# Display-Board_Rack-PDU_2_0.net
KiCad netlist of a schematic drawn in EAGLE
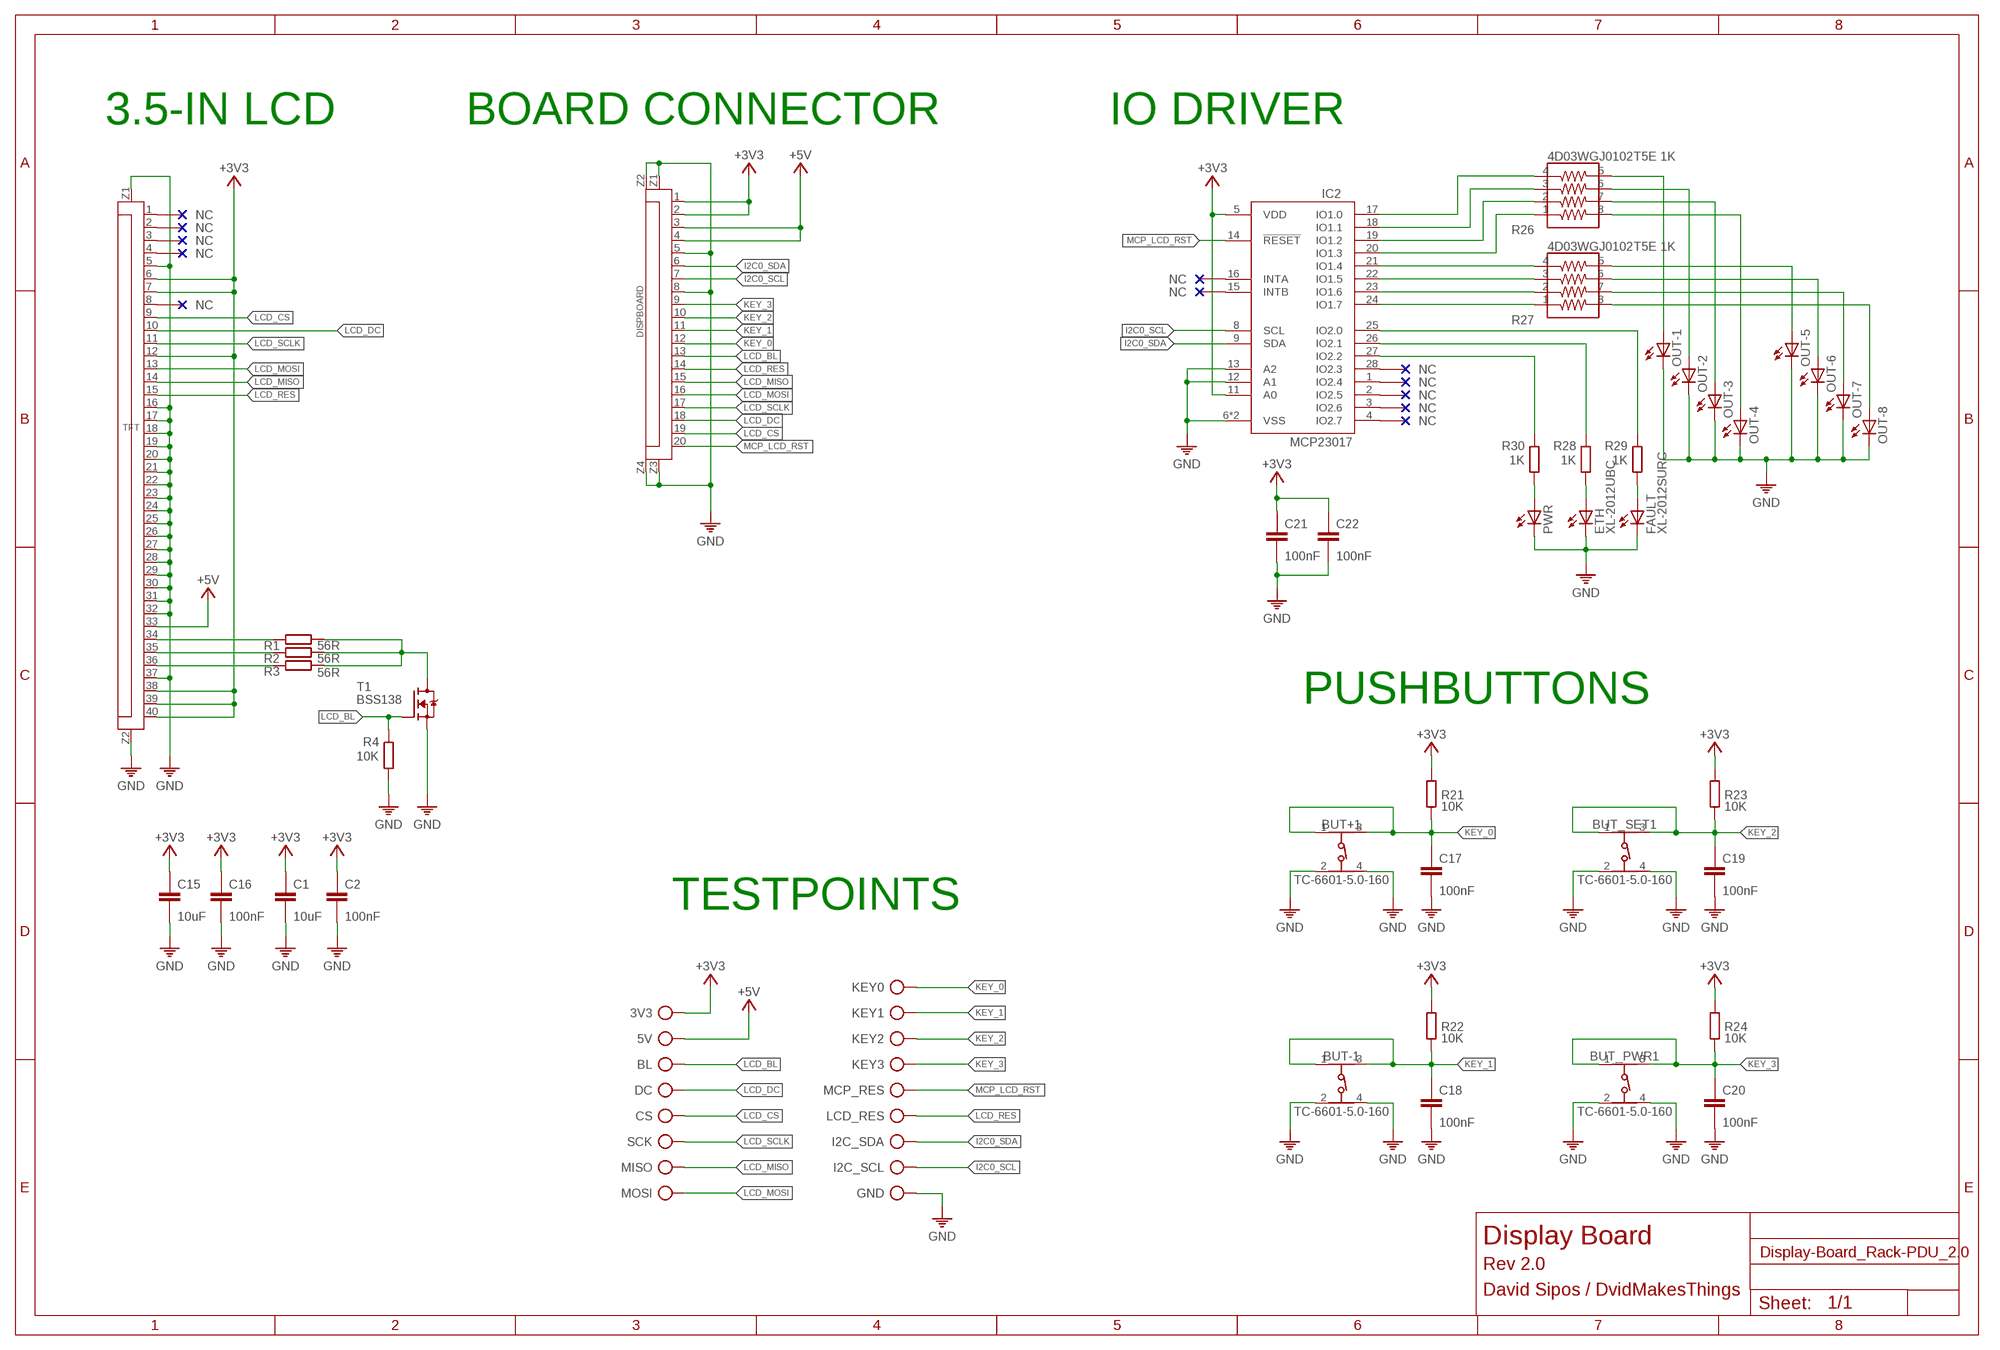
[diagram p0: schematic, sheet 1]

(export (version "E")
  (design (tool "Eeschema 10.0.6"))
  (components
    (comp (ref "3V3") (value "TP") (footprint "eagle-import:TP") (libsource (lib "eagle-import") (part "TP")))
    (comp (ref "5V") (value "TP") (footprint "eagle-import:TP") (libsource (lib "eagle-import") (part "TP")))
    (comp (ref "BL") (value "TP") (footprint "eagle-import:TP") (libsource (lib "eagle-import") (part "TP")))
    (comp (ref "BUT+1")
      (value "TC-6601-5.0-160")
      (footprint "eagle-import:430182043816")
      (libsource (lib "eagle-import") (part "430182043816"))
    )
    (comp (ref "BUT-1")
      (value "TC-6601-5.0-160")
      (footprint "eagle-import:430182043816")
      (libsource (lib "eagle-import") (part "430182043816"))
    )
    (comp (ref "BUT_PWR1")
      (value "TC-6601-5.0-160")
      (footprint "eagle-import:430182043816")
      (libsource (lib "eagle-import") (part "430182043816"))
    )
    (comp (ref "BUT_SET1")
      (value "TC-6601-5.0-160")
      (footprint "eagle-import:430182043816")
      (libsource (lib "eagle-import") (part "430182043816"))
    )
    (comp (ref "C1")
      (value "10uF")
      (footprint "eagle-import:C0402")
      (libsource (lib "eagle-import") (part "C-0402"))
    )
    (comp (ref "C2")
      (value "100nF")
      (footprint "eagle-import:C0402")
      (libsource (lib "eagle-import") (part "C-0402"))
    )
    (comp (ref "C15")
      (value "10uF")
      (footprint "eagle-import:C0402")
      (libsource (lib "eagle-import") (part "C-0402"))
    )
    (comp (ref "C16")
      (value "100nF")
      (footprint "eagle-import:C0402")
      (libsource (lib "eagle-import") (part "C-0402"))
    )
    (comp (ref "C17")
      (value "100nF")
      (footprint "eagle-import:C0402")
      (libsource (lib "eagle-import") (part "C-0402"))
    )
    (comp (ref "C18")
      (value "100nF")
      (footprint "eagle-import:C0402")
      (libsource (lib "eagle-import") (part "C-0402"))
    )
    (comp (ref "C19")
      (value "100nF")
      (footprint "eagle-import:C0402")
      (libsource (lib "eagle-import") (part "C-0402"))
    )
    (comp (ref "C20")
      (value "100nF")
      (footprint "eagle-import:C0402")
      (libsource (lib "eagle-import") (part "C-0402"))
    )
    (comp (ref "C21")
      (value "100nF")
      (footprint "eagle-import:C0402")
      (libsource (lib "eagle-import") (part "C-0402"))
    )
    (comp (ref "C22")
      (value "100nF")
      (footprint "eagle-import:C0402")
      (libsource (lib "eagle-import") (part "C-0402"))
    )
    (comp (ref "CS") (value "TP") (footprint "eagle-import:TP") (libsource (lib "eagle-import") (part "TP")))
    (comp (ref "DC") (value "TP") (footprint "eagle-import:TP") (libsource (lib "eagle-import") (part "TP")))
    (comp (ref "DISPBOARD")
      (value "FPC20-H")
      (footprint "eagle-import:FPC20")
      (libsource (lib "eagle-import") (part "FPC20-H"))
    )
    (comp (ref "ETH")
      (value "XL-2012UBC")
      (footprint "eagle-import:CHIP-LED0805")
      (libsource (lib "eagle-import") (part "LEDCHIP-LED0805"))
    )
    (comp (ref "FAULT")
      (value "XL-2012SURC")
      (footprint "eagle-import:CHIP-LED0805")
      (libsource (lib "eagle-import") (part "LEDCHIP-LED0805"))
    )
    (comp (ref "GND") (value "TP") (footprint "eagle-import:TP") (libsource (lib "eagle-import") (part "TP")))
    (comp (ref "I2C_SCL")
      (value "TP")
      (footprint "eagle-import:TP")
      (libsource (lib "eagle-import") (part "TP"))
    )
    (comp (ref "I2C_SDA")
      (value "TP")
      (footprint "eagle-import:TP")
      (libsource (lib "eagle-import") (part "TP"))
    )
    (comp (ref "IC2")
      (value "MCP23017-E/ML")
      (footprint "eagle-import:QFN28[6X6]ML")
      (libsource (lib "eagle-import") (part "MCP23017-E/ML"))
    )
    (comp (ref "KEY0")
      (value "TP")
      (footprint "eagle-import:TP")
      (libsource (lib "eagle-import") (part "TP"))
    )
    (comp (ref "KEY1")
      (value "TP")
      (footprint "eagle-import:TP")
      (libsource (lib "eagle-import") (part "TP"))
    )
    (comp (ref "KEY2")
      (value "TP")
      (footprint "eagle-import:TP")
      (libsource (lib "eagle-import") (part "TP"))
    )
    (comp (ref "KEY3")
      (value "TP")
      (footprint "eagle-import:TP")
      (libsource (lib "eagle-import") (part "TP"))
    )
    (comp (ref "LCD_RES")
      (value "TP")
      (footprint "eagle-import:TP")
      (libsource (lib "eagle-import") (part "TP"))
    )
    (comp (ref "MCP_RES")
      (value "TP")
      (footprint "eagle-import:TP")
      (libsource (lib "eagle-import") (part "TP"))
    )
    (comp (ref "MISO")
      (value "TP")
      (footprint "eagle-import:TP")
      (libsource (lib "eagle-import") (part "TP"))
    )
    (comp (ref "MOSI")
      (value "TP")
      (footprint "eagle-import:TP")
      (libsource (lib "eagle-import") (part "TP"))
    )
    (comp (ref "OUT-1")
      (value "LEDCHIP-LED0805")
      (footprint "eagle-import:CHIP-LED0805")
      (libsource (lib "eagle-import") (part "LEDCHIP-LED0805"))
    )
    (comp (ref "OUT-2")
      (value "LEDCHIP-LED0805")
      (footprint "eagle-import:CHIP-LED0805")
      (libsource (lib "eagle-import") (part "LEDCHIP-LED0805"))
    )
    (comp (ref "OUT-3")
      (value "LEDCHIP-LED0805")
      (footprint "eagle-import:CHIP-LED0805")
      (libsource (lib "eagle-import") (part "LEDCHIP-LED0805"))
    )
    (comp (ref "OUT-4")
      (value "LEDCHIP-LED0805")
      (footprint "eagle-import:CHIP-LED0805")
      (libsource (lib "eagle-import") (part "LEDCHIP-LED0805"))
    )
    (comp (ref "OUT-5")
      (value "LEDCHIP-LED0805")
      (footprint "eagle-import:CHIP-LED0805")
      (libsource (lib "eagle-import") (part "LEDCHIP-LED0805"))
    )
    (comp (ref "OUT-6")
      (value "LEDCHIP-LED0805")
      (footprint "eagle-import:CHIP-LED0805")
      (libsource (lib "eagle-import") (part "LEDCHIP-LED0805"))
    )
    (comp (ref "OUT-7")
      (value "LEDCHIP-LED0805")
      (footprint "eagle-import:CHIP-LED0805")
      (libsource (lib "eagle-import") (part "LEDCHIP-LED0805"))
    )
    (comp (ref "OUT-8")
      (value "LEDCHIP-LED0805")
      (footprint "eagle-import:CHIP-LED0805")
      (libsource (lib "eagle-import") (part "LEDCHIP-LED0805"))
    )
    (comp (ref "PWR")
      (value "LEDCHIP-LED0805")
      (footprint "eagle-import:CHIP-LED0805")
      (libsource (lib "eagle-import") (part "LEDCHIP-LED0805"))
    )
    (comp (ref "R1")
      (value "56R")
      (footprint "eagle-import:0402")
      (libsource (lib "eagle-import") (part "R0402"))
    )
    (comp (ref "R2")
      (value "56R")
      (footprint "eagle-import:0402")
      (libsource (lib "eagle-import") (part "R0402"))
    )
    (comp (ref "R3")
      (value "56R")
      (footprint "eagle-import:0402")
      (libsource (lib "eagle-import") (part "R0402"))
    )
    (comp (ref "R4")
      (value "10K")
      (footprint "eagle-import:0402")
      (libsource (lib "eagle-import") (part "R0402"))
    )
    (comp (ref "R21")
      (value "10K")
      (footprint "eagle-import:0402")
      (libsource (lib "eagle-import") (part "R0402"))
    )
    (comp (ref "R22")
      (value "10K")
      (footprint "eagle-import:0402")
      (libsource (lib "eagle-import") (part "R0402"))
    )
    (comp (ref "R23")
      (value "10K")
      (footprint "eagle-import:0402")
      (libsource (lib "eagle-import") (part "R0402"))
    )
    (comp (ref "R24")
      (value "10K")
      (footprint "eagle-import:0402")
      (libsource (lib "eagle-import") (part "R0402"))
    )
    (comp (ref "R26")
      (value "4D03WGJ0102T5E 1K")
      (footprint "eagle-import:742C083103JP")
      (fields
        (field (name "MANUFACTURER") "CTS Resistor Products")
        (field (name "MPN") "742C083103JP")
        (field (name "CREATED_BY") "PCBLayout.com")
      )
      (libsource (lib "eagle-import") (part "742C083103JP"))
    )
    (comp (ref "R27")
      (value "4D03WGJ0102T5E 1K")
      (footprint "eagle-import:742C083103JP")
      (fields
        (field (name "MANUFACTURER") "CTS Resistor Products")
        (field (name "MPN") "742C083103JP")
        (field (name "CREATED_BY") "PCBLayout.com")
      )
      (libsource (lib "eagle-import") (part "742C083103JP"))
    )
    (comp (ref "R28")
      (value "1K")
      (footprint "eagle-import:0402")
      (libsource (lib "eagle-import") (part "R0402"))
    )
    (comp (ref "R29")
      (value "1K")
      (footprint "eagle-import:0402")
      (libsource (lib "eagle-import") (part "R0402"))
    )
    (comp (ref "R30")
      (value "1K")
      (footprint "eagle-import:0402")
      (libsource (lib "eagle-import") (part "R0402"))
    )
    (comp (ref "SCK") (value "TP") (footprint "eagle-import:TP") (libsource (lib "eagle-import") (part "TP")))
    (comp (ref "T1")
      (value "BSS138")
      (footprint "eagle-import:SOT23")
      (libsource (lib "eagle-import") (part "BSS138"))
    )
    (comp (ref "TFT")
      (value "FPC40-HD")
      (footprint "eagle-import:FPC40_3.5TFT")
      (libsource (lib "eagle-import") (part "FPC40-HD"))
    )
  )
  (nets
    (net (code "1") (name "+3V3") (class "Default")
      (node (ref "3V3") (pin "TP") (pinfunction "P$1_TP") (pintype "bidirectional"))
      (node (ref "C1") (pin "1") (pinfunction "1_1") (pintype "passive"))
      (node (ref "C15") (pin "1") (pinfunction "1_1") (pintype "passive"))
      (node (ref "C16") (pin "1") (pinfunction "1_1") (pintype "passive"))
      (node (ref "C2") (pin "1") (pinfunction "1_1") (pintype "passive"))
      (node (ref "C21") (pin "1") (pinfunction "1_1") (pintype "passive"))
      (node (ref "C22") (pin "1") (pinfunction "1_1") (pintype "passive"))
      (node (ref "DISPBOARD") (pin "1") (pinfunction "1_1") (pintype "bidirectional"))
      (node (ref "DISPBOARD") (pin "2") (pinfunction "2_2") (pintype "bidirectional"))
      (node (ref "IC2") (pin "11") (pinfunction "A0_11") (pintype "bidirectional"))
      (node (ref "IC2") (pin "5") (pinfunction "VDD_5") (pintype "bidirectional"))
      (node (ref "R21") (pin "1") (pinfunction "1_1") (pintype "passive"))
      (node (ref "R22") (pin "1") (pinfunction "1_1") (pintype "passive"))
      (node (ref "R23") (pin "1") (pinfunction "1_1") (pintype "passive"))
      (node (ref "R24") (pin "1") (pinfunction "1_1") (pintype "passive"))
      (node (ref "TFT") (pin "12") (pinfunction "12_12") (pintype "bidirectional"))
      (node (ref "TFT") (pin "38") (pinfunction "38_38") (pintype "bidirectional"))
      (node (ref "TFT") (pin "39") (pinfunction "39_39") (pintype "bidirectional"))
      (node (ref "TFT") (pin "40") (pinfunction "40_40") (pintype "bidirectional"))
      (node (ref "TFT") (pin "6") (pinfunction "6_6") (pintype "bidirectional"))
      (node (ref "TFT") (pin "7") (pinfunction "7_7") (pintype "bidirectional"))
    )
    (net (code "2") (name "+5V") (class "Default")
      (node (ref "5V") (pin "TP") (pinfunction "P$1_TP") (pintype "bidirectional"))
      (node (ref "DISPBOARD") (pin "3") (pinfunction "3_3") (pintype "bidirectional"))
      (node (ref "DISPBOARD") (pin "4") (pinfunction "4_4") (pintype "bidirectional"))
      (node (ref "TFT") (pin "33") (pinfunction "33_33") (pintype "bidirectional"))
    )
    (net (code "3") (name "GND") (class "Default")
      (node (ref "BUT+1") (pin "2") (pinfunction "2_2") (pintype "passive"))
      (node (ref "BUT+1") (pin "4") (pinfunction "4_4") (pintype "passive"))
      (node (ref "BUT-1") (pin "2") (pinfunction "2_2") (pintype "passive"))
      (node (ref "BUT-1") (pin "4") (pinfunction "4_4") (pintype "passive"))
      (node (ref "BUT_PWR1") (pin "2") (pinfunction "2_2") (pintype "passive"))
      (node (ref "BUT_PWR1") (pin "4") (pinfunction "4_4") (pintype "passive"))
      (node (ref "BUT_SET1") (pin "2") (pinfunction "2_2") (pintype "passive"))
      (node (ref "BUT_SET1") (pin "4") (pinfunction "4_4") (pintype "passive"))
      (node (ref "C1") (pin "2") (pinfunction "2_2") (pintype "passive"))
      (node (ref "C15") (pin "2") (pinfunction "2_2") (pintype "passive"))
      (node (ref "C16") (pin "2") (pinfunction "2_2") (pintype "passive"))
      (node (ref "C17") (pin "2") (pinfunction "2_2") (pintype "passive"))
      (node (ref "C18") (pin "2") (pinfunction "2_2") (pintype "passive"))
      (node (ref "C19") (pin "2") (pinfunction "2_2") (pintype "passive"))
      (node (ref "C2") (pin "2") (pinfunction "2_2") (pintype "passive"))
      (node (ref "C20") (pin "2") (pinfunction "2_2") (pintype "passive"))
      (node (ref "C21") (pin "2") (pinfunction "2_2") (pintype "passive"))
      (node (ref "C22") (pin "2") (pinfunction "2_2") (pintype "passive"))
      (node (ref "DISPBOARD") (pin "5") (pinfunction "5_5") (pintype "bidirectional"))
      (node (ref "DISPBOARD") (pin "8") (pinfunction "8_8") (pintype "bidirectional"))
      (node (ref "DISPBOARD") (pin "Z1") (pinfunction "Z1_Z1") (pintype "bidirectional"))
      (node (ref "DISPBOARD") (pin "Z2") (pinfunction "Z2_Z2") (pintype "bidirectional"))
      (node (ref "DISPBOARD") (pin "Z3") (pinfunction "Z3_Z3") (pintype "bidirectional"))
      (node (ref "DISPBOARD") (pin "Z4") (pinfunction "Z4_Z4") (pintype "bidirectional"))
      (node (ref "ETH") (pin "C") (pinfunction "C_C") (pintype "passive"))
      (node (ref "FAULT") (pin "C") (pinfunction "C_C") (pintype "passive"))
      (node (ref "GND") (pin "TP") (pinfunction "P$1_TP") (pintype "bidirectional"))
      (node (ref "IC2") (pin "12") (pinfunction "A1_12") (pintype "bidirectional"))
      (node (ref "IC2") (pin "13") (pinfunction "A2_13") (pintype "bidirectional"))
      (node (ref "IC2") (pin "6") (pinfunction "VSS_6") (pintype "bidirectional"))
      (node (ref "IC2") (pin "PAD") (pinfunction "VSS_PAD") (pintype "bidirectional"))
      (node (ref "OUT-1") (pin "C") (pinfunction "C_C") (pintype "passive"))
      (node (ref "OUT-2") (pin "C") (pinfunction "C_C") (pintype "passive"))
      (node (ref "OUT-3") (pin "C") (pinfunction "C_C") (pintype "passive"))
      (node (ref "OUT-4") (pin "C") (pinfunction "C_C") (pintype "passive"))
      (node (ref "OUT-5") (pin "C") (pinfunction "C_C") (pintype "passive"))
      (node (ref "OUT-6") (pin "C") (pinfunction "C_C") (pintype "passive"))
      (node (ref "OUT-7") (pin "C") (pinfunction "C_C") (pintype "passive"))
      (node (ref "OUT-8") (pin "C") (pinfunction "C_C") (pintype "passive"))
      (node (ref "PWR") (pin "C") (pinfunction "C_C") (pintype "passive"))
      (node (ref "R4") (pin "2") (pinfunction "2_2") (pintype "passive"))
      (node (ref "T1") (pin "2") (pinfunction "S_2") (pintype "passive"))
      (node (ref "TFT") (pin "16") (pinfunction "16_16") (pintype "bidirectional"))
      (node (ref "TFT") (pin "17") (pinfunction "17_17") (pintype "bidirectional"))
      (node (ref "TFT") (pin "18") (pinfunction "18_18") (pintype "bidirectional"))
      (node (ref "TFT") (pin "19") (pinfunction "19_19") (pintype "bidirectional"))
      (node (ref "TFT") (pin "20") (pinfunction "20_20") (pintype "bidirectional"))
      (node (ref "TFT") (pin "21") (pinfunction "21_21") (pintype "bidirectional"))
      (node (ref "TFT") (pin "22") (pinfunction "22_22") (pintype "bidirectional"))
      (node (ref "TFT") (pin "23") (pinfunction "23_23") (pintype "bidirectional"))
      (node (ref "TFT") (pin "24") (pinfunction "24_24") (pintype "bidirectional"))
      (node (ref "TFT") (pin "25") (pinfunction "25_25") (pintype "bidirectional"))
      (node (ref "TFT") (pin "26") (pinfunction "26_26") (pintype "bidirectional"))
      (node (ref "TFT") (pin "27") (pinfunction "27_27") (pintype "bidirectional"))
      (node (ref "TFT") (pin "28") (pinfunction "28_28") (pintype "bidirectional"))
      (node (ref "TFT") (pin "29") (pinfunction "29_29") (pintype "bidirectional"))
      (node (ref "TFT") (pin "30") (pinfunction "30_30") (pintype "bidirectional"))
      (node (ref "TFT") (pin "31") (pinfunction "31_31") (pintype "bidirectional"))
      (node (ref "TFT") (pin "32") (pinfunction "32_32") (pintype "bidirectional"))
      (node (ref "TFT") (pin "37") (pinfunction "37_37") (pintype "bidirectional"))
      (node (ref "TFT") (pin "5") (pinfunction "5_5") (pintype "bidirectional"))
      (node (ref "TFT") (pin "Z1") (pinfunction "Z1_Z1") (pintype "bidirectional"))
      (node (ref "TFT") (pin "Z2") (pinfunction "Z2_Z2") (pintype "bidirectional"))
    )
    (net (code "4") (name "I2C0_SCL") (class "Default")
      (node (ref "DISPBOARD") (pin "7") (pinfunction "7_7") (pintype "bidirectional"))
      (node (ref "I2C_SCL") (pin "TP") (pinfunction "P$1_TP") (pintype "bidirectional"))
      (node (ref "IC2") (pin "8") (pinfunction "SCL_8") (pintype "bidirectional"))
    )
    (net (code "5") (name "I2C0_SDA") (class "Default")
      (node (ref "DISPBOARD") (pin "6") (pinfunction "6_6") (pintype "bidirectional"))
      (node (ref "I2C_SDA") (pin "TP") (pinfunction "P$1_TP") (pintype "bidirectional"))
      (node (ref "IC2") (pin "9") (pinfunction "SDA_9") (pintype "bidirectional"))
    )
    (net (code "6") (name "KEY_0") (class "Default")
      (node (ref "BUT+1") (pin "1") (pinfunction "1_1") (pintype "passive"))
      (node (ref "BUT+1") (pin "3") (pinfunction "3_3") (pintype "passive"))
      (node (ref "C17") (pin "1") (pinfunction "1_1") (pintype "passive"))
      (node (ref "DISPBOARD") (pin "12") (pinfunction "12_12") (pintype "bidirectional"))
      (node (ref "KEY0") (pin "TP") (pinfunction "P$1_TP") (pintype "bidirectional"))
      (node (ref "R21") (pin "2") (pinfunction "2_2") (pintype "passive"))
    )
    (net (code "7") (name "KEY_1") (class "Default")
      (node (ref "BUT-1") (pin "1") (pinfunction "1_1") (pintype "passive"))
      (node (ref "BUT-1") (pin "3") (pinfunction "3_3") (pintype "passive"))
      (node (ref "C18") (pin "1") (pinfunction "1_1") (pintype "passive"))
      (node (ref "DISPBOARD") (pin "11") (pinfunction "11_11") (pintype "bidirectional"))
      (node (ref "KEY1") (pin "TP") (pinfunction "P$1_TP") (pintype "bidirectional"))
      (node (ref "R22") (pin "2") (pinfunction "2_2") (pintype "passive"))
    )
    (net (code "8") (name "KEY_2") (class "Default")
      (node (ref "BUT_SET1") (pin "1") (pinfunction "1_1") (pintype "passive"))
      (node (ref "BUT_SET1") (pin "3") (pinfunction "3_3") (pintype "passive"))
      (node (ref "C19") (pin "1") (pinfunction "1_1") (pintype "passive"))
      (node (ref "DISPBOARD") (pin "10") (pinfunction "10_10") (pintype "bidirectional"))
      (node (ref "KEY2") (pin "TP") (pinfunction "P$1_TP") (pintype "bidirectional"))
      (node (ref "R23") (pin "2") (pinfunction "2_2") (pintype "passive"))
    )
    (net (code "9") (name "KEY_3") (class "Default")
      (node (ref "BUT_PWR1") (pin "1") (pinfunction "1_1") (pintype "passive"))
      (node (ref "BUT_PWR1") (pin "3") (pinfunction "3_3") (pintype "passive"))
      (node (ref "C20") (pin "1") (pinfunction "1_1") (pintype "passive"))
      (node (ref "DISPBOARD") (pin "9") (pinfunction "9_9") (pintype "bidirectional"))
      (node (ref "KEY3") (pin "TP") (pinfunction "P$1_TP") (pintype "bidirectional"))
      (node (ref "R24") (pin "2") (pinfunction "2_2") (pintype "passive"))
    )
    (net (code "10") (name "LCD_BL") (class "Default")
      (node (ref "BL") (pin "TP") (pinfunction "P$1_TP") (pintype "bidirectional"))
      (node (ref "DISPBOARD") (pin "13") (pinfunction "13_13") (pintype "bidirectional"))
      (node (ref "R4") (pin "1") (pinfunction "1_1") (pintype "passive"))
      (node (ref "T1") (pin "1") (pinfunction "G_1") (pintype "passive"))
    )
    (net (code "11") (name "LCD_CS") (class "Default")
      (node (ref "CS") (pin "TP") (pinfunction "P$1_TP") (pintype "bidirectional"))
      (node (ref "DISPBOARD") (pin "19") (pinfunction "19_19") (pintype "bidirectional"))
      (node (ref "TFT") (pin "9") (pinfunction "9_9") (pintype "bidirectional"))
    )
    (net (code "12") (name "LCD_DC") (class "Default")
      (node (ref "DC") (pin "TP") (pinfunction "P$1_TP") (pintype "bidirectional"))
      (node (ref "DISPBOARD") (pin "18") (pinfunction "18_18") (pintype "bidirectional"))
      (node (ref "TFT") (pin "10") (pinfunction "10_10") (pintype "bidirectional"))
    )
    (net (code "13") (name "LCD_MISO") (class "Default")
      (node (ref "DISPBOARD") (pin "15") (pinfunction "15_15") (pintype "bidirectional"))
      (node (ref "MISO") (pin "TP") (pinfunction "P$1_TP") (pintype "bidirectional"))
      (node (ref "TFT") (pin "14") (pinfunction "14_14") (pintype "bidirectional"))
    )
    (net (code "14") (name "LCD_MOSI") (class "Default")
      (node (ref "DISPBOARD") (pin "16") (pinfunction "16_16") (pintype "bidirectional"))
      (node (ref "MOSI") (pin "TP") (pinfunction "P$1_TP") (pintype "bidirectional"))
      (node (ref "TFT") (pin "13") (pinfunction "13_13") (pintype "bidirectional"))
    )
    (net (code "15") (name "LCD_RES") (class "Default")
      (node (ref "DISPBOARD") (pin "14") (pinfunction "14_14") (pintype "bidirectional"))
      (node (ref "LCD_RES") (pin "TP") (pinfunction "P$1_TP") (pintype "bidirectional"))
      (node (ref "TFT") (pin "15") (pinfunction "15_15") (pintype "bidirectional"))
    )
    (net (code "16") (name "LCD_SCLK") (class "Default")
      (node (ref "DISPBOARD") (pin "17") (pinfunction "17_17") (pintype "bidirectional"))
      (node (ref "SCK") (pin "TP") (pinfunction "P$1_TP") (pintype "bidirectional"))
      (node (ref "TFT") (pin "11") (pinfunction "11_11") (pintype "bidirectional"))
    )
    (net (code "17") (name "MCP_LCD_RST") (class "Default")
      (node (ref "DISPBOARD") (pin "20") (pinfunction "20_20") (pintype "bidirectional"))
      (node (ref "IC2") (pin "14") (pinfunction "~{RESET}_14") (pintype "bidirectional"))
      (node (ref "MCP_RES") (pin "TP") (pinfunction "P$1_TP") (pintype "bidirectional"))
    )
    (net (code "18") (name "Net-(ETH-PadA)") (class "Default")
      (node (ref "ETH") (pin "A") (pinfunction "A_A") (pintype "passive"))
      (node (ref "R28") (pin "2") (pinfunction "2_2") (pintype "passive"))
    )
    (net (code "19") (name "Net-(FAULT-PadA)") (class "Default")
      (node (ref "FAULT") (pin "A") (pinfunction "A_A") (pintype "passive"))
      (node (ref "R29") (pin "2") (pinfunction "2_2") (pintype "passive"))
    )
    (net (code "20") (name "Net-(IC2-IO1.0)") (class "Default")
      (node (ref "IC2") (pin "17") (pinfunction "IO1.0_17") (pintype "bidirectional"))
      (node (ref "R26") (pin "4") (pinfunction "4_4") (pintype "passive"))
    )
    (net (code "21") (name "Net-(IC2-IO1.1)") (class "Default")
      (node (ref "IC2") (pin "18") (pinfunction "IO1.1_18") (pintype "bidirectional"))
      (node (ref "R26") (pin "3") (pinfunction "3_3") (pintype "passive"))
    )
    (net (code "22") (name "Net-(IC2-IO1.2)") (class "Default")
      (node (ref "IC2") (pin "19") (pinfunction "IO1.2_19") (pintype "bidirectional"))
      (node (ref "R26") (pin "2") (pinfunction "2_2") (pintype "passive"))
    )
    (net (code "23") (name "Net-(IC2-IO1.3)") (class "Default")
      (node (ref "IC2") (pin "20") (pinfunction "IO1.3_20") (pintype "bidirectional"))
      (node (ref "R26") (pin "1") (pinfunction "1_1") (pintype "passive"))
    )
    (net (code "24") (name "Net-(IC2-IO1.4)") (class "Default")
      (node (ref "IC2") (pin "21") (pinfunction "IO1.4_21") (pintype "bidirectional"))
      (node (ref "R27") (pin "4") (pinfunction "4_4") (pintype "passive"))
    )
    (net (code "25") (name "Net-(IC2-IO1.5)") (class "Default")
      (node (ref "IC2") (pin "22") (pinfunction "IO1.5_22") (pintype "bidirectional"))
      (node (ref "R27") (pin "3") (pinfunction "3_3") (pintype "passive"))
    )
    (net (code "26") (name "Net-(IC2-IO1.6)") (class "Default")
      (node (ref "IC2") (pin "23") (pinfunction "IO1.6_23") (pintype "bidirectional"))
      (node (ref "R27") (pin "2") (pinfunction "2_2") (pintype "passive"))
    )
    (net (code "27") (name "Net-(IC2-IO1.7)") (class "Default")
      (node (ref "IC2") (pin "24") (pinfunction "IO1.7_24") (pintype "bidirectional"))
      (node (ref "R27") (pin "1") (pinfunction "1_1") (pintype "passive"))
    )
    (net (code "28") (name "Net-(IC2-IO2.0)") (class "Default")
      (node (ref "IC2") (pin "25") (pinfunction "IO2.0_25") (pintype "bidirectional"))
      (node (ref "R29") (pin "1") (pinfunction "1_1") (pintype "passive"))
    )
    (net (code "29") (name "Net-(IC2-IO2.1)") (class "Default")
      (node (ref "IC2") (pin "26") (pinfunction "IO2.1_26") (pintype "bidirectional"))
      (node (ref "R28") (pin "1") (pinfunction "1_1") (pintype "passive"))
    )
    (net (code "30") (name "Net-(IC2-IO2.2)") (class "Default")
      (node (ref "IC2") (pin "27") (pinfunction "IO2.2_27") (pintype "bidirectional"))
      (node (ref "R30") (pin "1") (pinfunction "1_1") (pintype "passive"))
    )
    (net (code "31") (name "Net-(OUT-1-PadA)") (class "Default")
      (node (ref "OUT-1") (pin "A") (pinfunction "A_A") (pintype "passive"))
      (node (ref "R26") (pin "5") (pinfunction "5_5") (pintype "passive"))
    )
    (net (code "32") (name "Net-(OUT-2-PadA)") (class "Default")
      (node (ref "OUT-2") (pin "A") (pinfunction "A_A") (pintype "passive"))
      (node (ref "R26") (pin "6") (pinfunction "6_6") (pintype "passive"))
    )
    (net (code "33") (name "Net-(OUT-3-PadA)") (class "Default")
      (node (ref "OUT-3") (pin "A") (pinfunction "A_A") (pintype "passive"))
      (node (ref "R26") (pin "7") (pinfunction "7_7") (pintype "passive"))
    )
    (net (code "34") (name "Net-(OUT-4-PadA)") (class "Default")
      (node (ref "OUT-4") (pin "A") (pinfunction "A_A") (pintype "passive"))
      (node (ref "R26") (pin "8") (pinfunction "8_8") (pintype "passive"))
    )
    (net (code "35") (name "Net-(OUT-5-PadA)") (class "Default")
      (node (ref "OUT-5") (pin "A") (pinfunction "A_A") (pintype "passive"))
      (node (ref "R27") (pin "5") (pinfunction "5_5") (pintype "passive"))
    )
    (net (code "36") (name "Net-(OUT-6-PadA)") (class "Default")
      (node (ref "OUT-6") (pin "A") (pinfunction "A_A") (pintype "passive"))
      (node (ref "R27") (pin "6") (pinfunction "6_6") (pintype "passive"))
    )
    (net (code "37") (name "Net-(OUT-7-PadA)") (class "Default")
      (node (ref "OUT-7") (pin "A") (pinfunction "A_A") (pintype "passive"))
      (node (ref "R27") (pin "7") (pinfunction "7_7") (pintype "passive"))
    )
    (net (code "38") (name "Net-(OUT-8-PadA)") (class "Default")
      (node (ref "OUT-8") (pin "A") (pinfunction "A_A") (pintype "passive"))
      (node (ref "R27") (pin "8") (pinfunction "8_8") (pintype "passive"))
    )
    (net (code "39") (name "Net-(PWR-PadA)") (class "Default")
      (node (ref "PWR") (pin "A") (pinfunction "A_A") (pintype "passive"))
      (node (ref "R30") (pin "2") (pinfunction "2_2") (pintype "passive"))
    )
    (net (code "40") (name "Net-(R1-Pad2)") (class "Default")
      (node (ref "R1") (pin "2") (pinfunction "2_2") (pintype "passive"))
      (node (ref "TFT") (pin "34") (pinfunction "34_34") (pintype "bidirectional"))
    )
    (net (code "41") (name "Net-(R2-Pad2)") (class "Default")
      (node (ref "R2") (pin "2") (pinfunction "2_2") (pintype "passive"))
      (node (ref "TFT") (pin "35") (pinfunction "35_35") (pintype "bidirectional"))
    )
    (net (code "42") (name "Net-(R3-Pad2)") (class "Default")
      (node (ref "R3") (pin "2") (pinfunction "2_2") (pintype "passive"))
      (node (ref "TFT") (pin "36") (pinfunction "36_36") (pintype "bidirectional"))
    )
    (net (code "43") (name "Net-(T1-D)") (class "Default")
      (node (ref "R1") (pin "1") (pinfunction "1_1") (pintype "passive"))
      (node (ref "R2") (pin "1") (pinfunction "1_1") (pintype "passive"))
      (node (ref "R3") (pin "1") (pinfunction "1_1") (pintype "passive"))
      (node (ref "T1") (pin "3") (pinfunction "D_3") (pintype "passive"))
    )
    (net (code "44") (name "unconnected-(IC2-INTA-Pad16)") (class "Default")
      (node (ref "IC2") (pin "16") (pinfunction "INTA_16") (pintype "bidirectional"))
    )
    (net (code "45") (name "unconnected-(IC2-INTB-Pad15)") (class "Default")
      (node (ref "IC2") (pin "15") (pinfunction "INTB_15") (pintype "bidirectional"))
    )
    (net (code "46") (name "unconnected-(IC2-IO2.3-Pad28)") (class "Default")
      (node (ref "IC2") (pin "28") (pinfunction "IO2.3_28") (pintype "bidirectional"))
    )
    (net (code "47") (name "unconnected-(IC2-IO2.4-Pad1)") (class "Default")
      (node (ref "IC2") (pin "1") (pinfunction "IO2.4_1") (pintype "bidirectional"))
    )
    (net (code "48") (name "unconnected-(IC2-IO2.5-Pad2)") (class "Default")
      (node (ref "IC2") (pin "2") (pinfunction "IO2.5_2") (pintype "bidirectional"))
    )
    (net (code "49") (name "unconnected-(IC2-IO2.6-Pad3)") (class "Default")
      (node (ref "IC2") (pin "3") (pinfunction "IO2.6_3") (pintype "bidirectional"))
    )
    (net (code "50") (name "unconnected-(IC2-IO2.7-Pad4)") (class "Default")
      (node (ref "IC2") (pin "4") (pinfunction "IO2.7_4") (pintype "bidirectional"))
    )
    (net (code "51") (name "unconnected-(TFT-Pad1)") (class "Default")
      (node (ref "TFT") (pin "1") (pinfunction "1_1") (pintype "bidirectional"))
    )
    (net (code "52") (name "unconnected-(TFT-Pad2)") (class "Default")
      (node (ref "TFT") (pin "2") (pinfunction "2_2") (pintype "bidirectional"))
    )
    (net (code "53") (name "unconnected-(TFT-Pad3)") (class "Default")
      (node (ref "TFT") (pin "3") (pinfunction "3_3") (pintype "bidirectional"))
    )
    (net (code "54") (name "unconnected-(TFT-Pad4)") (class "Default")
      (node (ref "TFT") (pin "4") (pinfunction "4_4") (pintype "bidirectional"))
    )
    (net (code "55") (name "unconnected-(TFT-Pad8)") (class "Default")
      (node (ref "TFT") (pin "8") (pinfunction "8_8") (pintype "bidirectional"))
    )
  )
)
